# ControlPanel.net
KiCad netlist of a schematic drawn in EAGLE
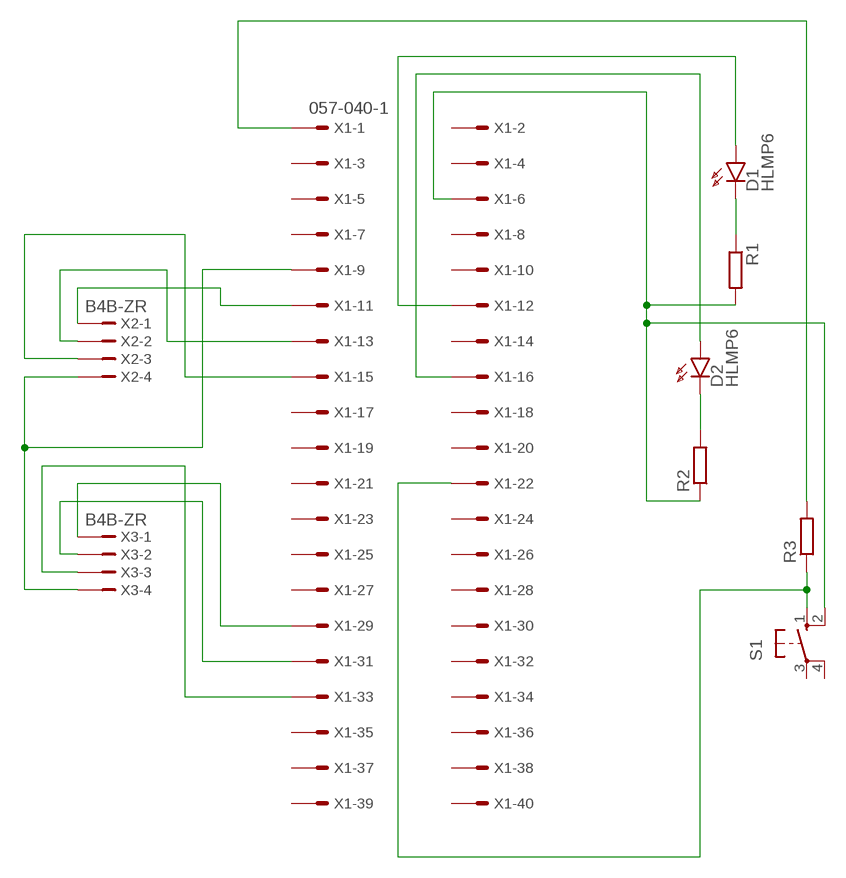
[diagram p0: schematic, sheet 1]

(export (version "E")
  (design (tool "Eeschema 10.0.6"))
  (components
    (comp (ref "D1")
      (value "HLMP6")
      (footprint "eagle-import:HLMP6")
      (fields (field (name "MF") "AGILENT TECHNOLOGIES") (field (name "MPN") "HLMP-6500"))
      (libsource (lib "eagle-import") (part "HLMP6"))
    )
    (comp (ref "D2")
      (value "HLMP6")
      (footprint "eagle-import:HLMP6")
      (fields (field (name "MF") "AGILENT TECHNOLOGIES") (field (name "MPN") "HLMP-6500"))
      (libsource (lib "eagle-import") (part "HLMP6"))
    )
    (comp (ref "R1")
      (value "R-EU_0204/7")
      (footprint "eagle-import:0204_7")
      (libsource (lib "eagle-import") (part "R-EU_0204/7"))
    )
    (comp (ref "R2")
      (value "R-EU_0204/7")
      (footprint "eagle-import:0204_7")
      (libsource (lib "eagle-import") (part "R-EU_0204/7"))
    )
    (comp (ref "R3")
      (value "R-EU_0204/7")
      (footprint "eagle-import:0204_7")
      (libsource (lib "eagle-import") (part "R-EU_0204/7"))
    )
    (comp (ref "S1")
      (value "10-XX")
      (footprint "eagle-import:B3F-10XX")
      (fields (field (name "MPN") "B3F-1000"))
      (libsource (lib "eagle-import") (part "10-XX"))
    )
    (comp (ref "X1")
      (value "057-040-1")
      (footprint "eagle-import:057-040-1")
      (libsource (lib "eagle-import") (part "057-040-1"))
    )
    (comp (ref "X2")
      (value "B4B-ZR")
      (footprint "eagle-import:B4B-ZR")
      (fields (field (name "MF") "FARNELL") (field (name "MPN") "B4B-ZR(LF)(SN)"))
      (libsource (lib "eagle-import") (part "?4B-ZRB"))
    )
    (comp (ref "X3")
      (value "B4B-ZR")
      (footprint "eagle-import:B4B-ZR")
      (fields (field (name "MF") "FARNELL") (field (name "MPN") "B4B-ZR(LF)(SN)"))
      (libsource (lib "eagle-import") (part "?4B-ZRB"))
    )
  )
  (nets
    (net (code "1") (name "Net-(D1-PadK)") (class "Default")
      (node (ref "D1") (pin "K") (pinfunction "K_K") (pintype "passive"))
      (node (ref "R1") (pin "1") (pinfunction "1_1") (pintype "passive"))
    )
    (net (code "2") (name "Net-(D2-PadK)") (class "Default")
      (node (ref "D2") (pin "K") (pinfunction "K_K") (pintype "passive"))
      (node (ref "R2") (pin "2") (pinfunction "2_2") (pintype "passive"))
    )
    (net (code "3") (name "Net-(S1-S)") (class "Default")
      (node (ref "R3") (pin "1") (pinfunction "1_1") (pintype "passive"))
      (node (ref "S1") (pin "1") (pinfunction "S_1") (pintype "passive"))
      (node (ref "X1") (pin "22") (pinfunction "S_22") (pintype "passive"))
    )
    (net (code "4") (name "Net-(S1-S1)") (class "Default")
      (node (ref "R1") (pin "2") (pinfunction "2_2") (pintype "passive"))
      (node (ref "R2") (pin "1") (pinfunction "1_1") (pintype "passive"))
      (node (ref "S1") (pin "2") (pinfunction "S1_2") (pintype "passive"))
      (node (ref "X1") (pin "6") (pinfunction "S_6") (pintype "passive"))
    )
    (net (code "5") (name "Net-(X1A-S)") (class "Default")
      (node (ref "R3") (pin "2") (pinfunction "2_2") (pintype "passive"))
      (node (ref "X1") (pin "1") (pinfunction "S_1") (pintype "passive"))
    )
    (net (code "6") (name "Net-(X1AA-S)") (class "Default")
      (node (ref "X1") (pin "33") (pinfunction "S_33") (pintype "passive"))
      (node (ref "X3") (pin "3") (pinfunction "1_3") (pintype "passive"))
    )
    (net (code "7") (name "Net-(X1AN-S)") (class "Default")
      (node (ref "X1") (pin "9") (pinfunction "S_9") (pintype "passive"))
      (node (ref "X2") (pin "4") (pinfunction "1_4") (pintype "passive"))
      (node (ref "X3") (pin "4") (pinfunction "1_4") (pintype "passive"))
    )
    (net (code "8") (name "Net-(X1C-S)") (class "Default")
      (node (ref "X1") (pin "11") (pinfunction "S_11") (pintype "passive"))
      (node (ref "X2") (pin "1") (pinfunction "1_1") (pintype "passive"))
    )
    (net (code "9") (name "Net-(X1D-S)") (class "Default")
      (node (ref "D1") (pin "A") (pinfunction "A_A") (pintype "passive"))
      (node (ref "X1") (pin "12") (pinfunction "S_12") (pintype "passive"))
    )
    (net (code "10") (name "Net-(X1E-S)") (class "Default")
      (node (ref "X1") (pin "13") (pinfunction "S_13") (pintype "passive"))
      (node (ref "X2") (pin "2") (pinfunction "1_2") (pintype "passive"))
    )
    (net (code "11") (name "Net-(X1G-S)") (class "Default")
      (node (ref "X1") (pin "15") (pinfunction "S_15") (pintype "passive"))
      (node (ref "X2") (pin "3") (pinfunction "1_3") (pintype "passive"))
    )
    (net (code "12") (name "Net-(X1H-S)") (class "Default")
      (node (ref "D2") (pin "A") (pinfunction "A_A") (pintype "passive"))
      (node (ref "X1") (pin "16") (pinfunction "S_16") (pintype "passive"))
    )
    (net (code "13") (name "Net-(X1V-S)") (class "Default")
      (node (ref "X1") (pin "29") (pinfunction "S_29") (pintype "passive"))
      (node (ref "X3") (pin "1") (pinfunction "1_1") (pintype "passive"))
    )
    (net (code "14") (name "Net-(X1Y-S)") (class "Default")
      (node (ref "X1") (pin "31") (pinfunction "S_31") (pintype "passive"))
      (node (ref "X3") (pin "2") (pinfunction "1_2") (pintype "passive"))
    )
    (net (code "15") (name "unconnected-(S1-P-Pad3)") (class "Default")
      (node (ref "S1") (pin "3") (pinfunction "P_3") (pintype "passive"))
    )
    (net (code "16") (name "unconnected-(S1-P1-Pad4)") (class "Default")
      (node (ref "S1") (pin "4") (pinfunction "P1_4") (pintype "passive"))
    )
    (net (code "17") (name "unconnected-(X1AB-S-Pad34)") (class "Default")
      (node (ref "X1") (pin "34") (pinfunction "S_34") (pintype "passive"))
    )
    (net (code "18") (name "unconnected-(X1AC-S-Pad35)") (class "Default")
      (node (ref "X1") (pin "35") (pinfunction "S_35") (pintype "passive"))
    )
    (net (code "19") (name "unconnected-(X1AD-S-Pad36)") (class "Default")
      (node (ref "X1") (pin "36") (pinfunction "S_36") (pintype "passive"))
    )
    (net (code "20") (name "unconnected-(X1AE-S-Pad37)") (class "Default")
      (node (ref "X1") (pin "37") (pinfunction "S_37") (pintype "passive"))
    )
    (net (code "21") (name "unconnected-(X1AF-S-Pad38)") (class "Default")
      (node (ref "X1") (pin "38") (pinfunction "S_38") (pintype "passive"))
    )
    (net (code "22") (name "unconnected-(X1AG-S-Pad39)") (class "Default")
      (node (ref "X1") (pin "39") (pinfunction "S_39") (pintype "passive"))
    )
    (net (code "23") (name "unconnected-(X1AH-S-Pad4)") (class "Default")
      (node (ref "X1") (pin "4") (pinfunction "S_4") (pintype "passive"))
    )
    (net (code "24") (name "unconnected-(X1AI-S-Pad40)") (class "Default")
      (node (ref "X1") (pin "40") (pinfunction "S_40") (pintype "passive"))
    )
    (net (code "25") (name "unconnected-(X1AJ-S-Pad5)") (class "Default")
      (node (ref "X1") (pin "5") (pinfunction "S_5") (pintype "passive"))
    )
    (net (code "26") (name "unconnected-(X1AL-S-Pad7)") (class "Default")
      (node (ref "X1") (pin "7") (pinfunction "S_7") (pintype "passive"))
    )
    (net (code "27") (name "unconnected-(X1AM-S-Pad8)") (class "Default")
      (node (ref "X1") (pin "8") (pinfunction "S_8") (pintype "passive"))
    )
    (net (code "28") (name "unconnected-(X1B-S-Pad10)") (class "Default")
      (node (ref "X1") (pin "10") (pinfunction "S_10") (pintype "passive"))
    )
    (net (code "29") (name "unconnected-(X1F-S-Pad14)") (class "Default")
      (node (ref "X1") (pin "14") (pinfunction "S_14") (pintype "passive"))
    )
    (net (code "30") (name "unconnected-(X1I-S-Pad17)") (class "Default")
      (node (ref "X1") (pin "17") (pinfunction "S_17") (pintype "passive"))
    )
    (net (code "31") (name "unconnected-(X1J-S-Pad18)") (class "Default")
      (node (ref "X1") (pin "18") (pinfunction "S_18") (pintype "passive"))
    )
    (net (code "32") (name "unconnected-(X1K-S-Pad19)") (class "Default")
      (node (ref "X1") (pin "19") (pinfunction "S_19") (pintype "passive"))
    )
    (net (code "33") (name "unconnected-(X1L-S-Pad2)") (class "Default")
      (node (ref "X1") (pin "2") (pinfunction "S_2") (pintype "passive"))
    )
    (net (code "34") (name "unconnected-(X1M-S-Pad20)") (class "Default")
      (node (ref "X1") (pin "20") (pinfunction "S_20") (pintype "passive"))
    )
    (net (code "35") (name "unconnected-(X1N-S-Pad21)") (class "Default")
      (node (ref "X1") (pin "21") (pinfunction "S_21") (pintype "passive"))
    )
    (net (code "36") (name "unconnected-(X1P-S-Pad23)") (class "Default")
      (node (ref "X1") (pin "23") (pinfunction "S_23") (pintype "passive"))
    )
    (net (code "37") (name "unconnected-(X1Q-S-Pad24)") (class "Default")
      (node (ref "X1") (pin "24") (pinfunction "S_24") (pintype "passive"))
    )
    (net (code "38") (name "unconnected-(X1R-S-Pad25)") (class "Default")
      (node (ref "X1") (pin "25") (pinfunction "S_25") (pintype "passive"))
    )
    (net (code "39") (name "unconnected-(X1S-S-Pad26)") (class "Default")
      (node (ref "X1") (pin "26") (pinfunction "S_26") (pintype "passive"))
    )
    (net (code "40") (name "unconnected-(X1T-S-Pad27)") (class "Default")
      (node (ref "X1") (pin "27") (pinfunction "S_27") (pintype "passive"))
    )
    (net (code "41") (name "unconnected-(X1U-S-Pad28)") (class "Default")
      (node (ref "X1") (pin "28") (pinfunction "S_28") (pintype "passive"))
    )
    (net (code "42") (name "unconnected-(X1W-S-Pad3)") (class "Default")
      (node (ref "X1") (pin "3") (pinfunction "S_3") (pintype "passive"))
    )
    (net (code "43") (name "unconnected-(X1X-S-Pad30)") (class "Default")
      (node (ref "X1") (pin "30") (pinfunction "S_30") (pintype "passive"))
    )
    (net (code "44") (name "unconnected-(X1Z-S-Pad32)") (class "Default")
      (node (ref "X1") (pin "32") (pinfunction "S_32") (pintype "passive"))
    )
  )
)
